# PISTA.net
KiCad netlist of a schematic drawn in EAGLE
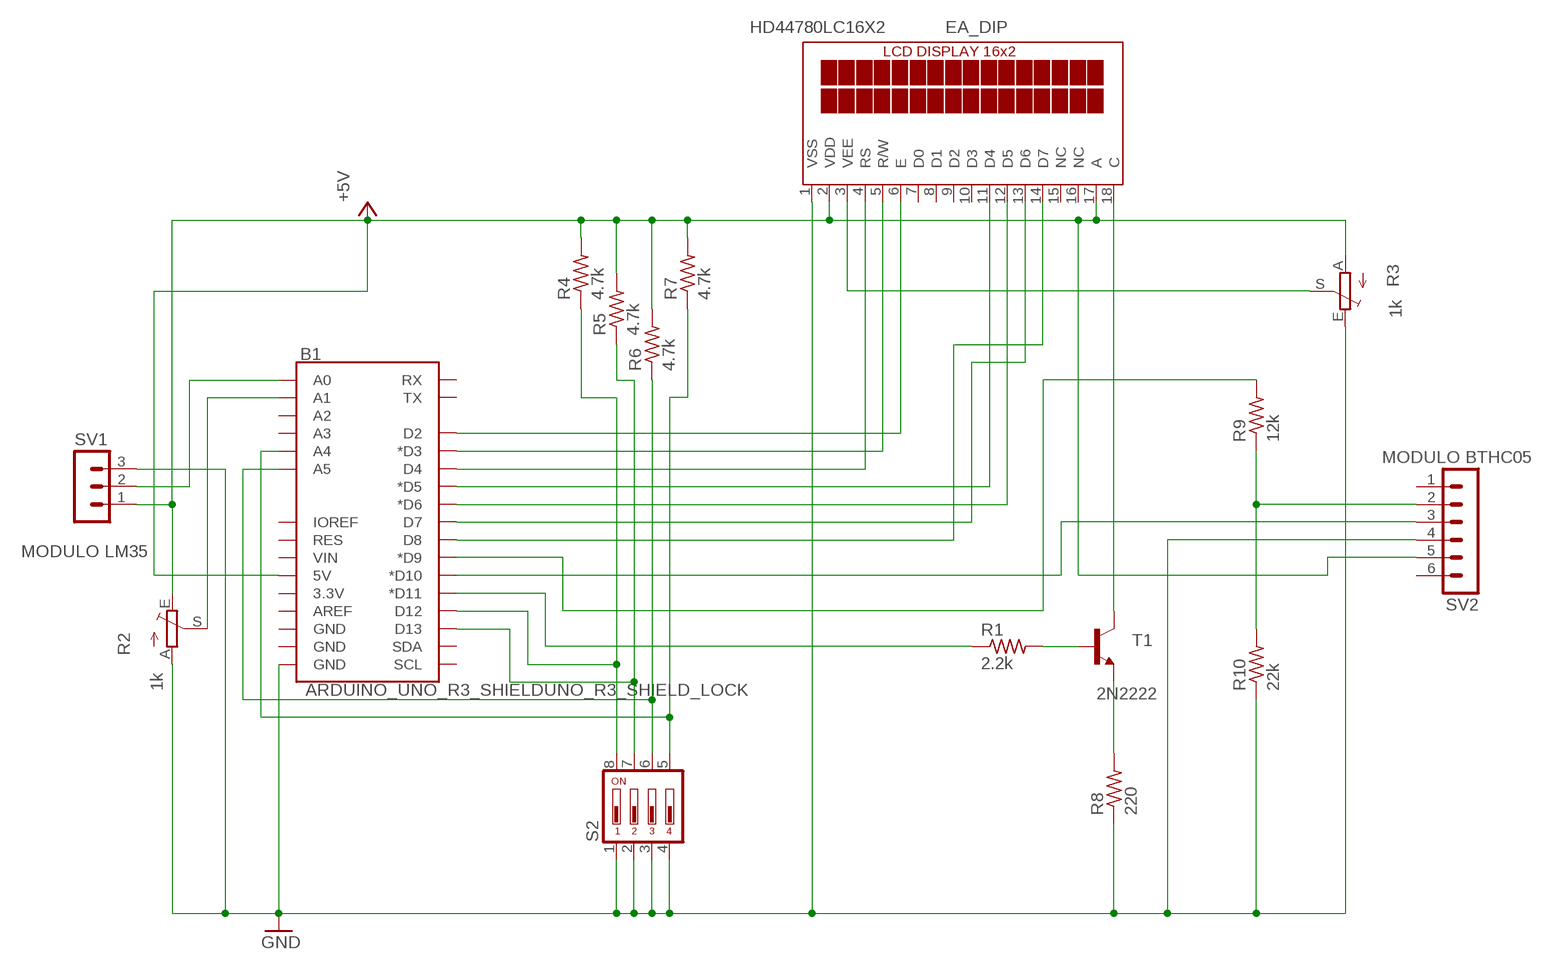
[diagram p0: schematic, sheet 1]

(export (version "E")
  (design (tool "Eeschema 10.0.6"))
  (components
    (comp (ref "B1")
      (value "ARDUINO_UNO_R3_SHIELDUNO_R3_SHIELD_LOCK")
      (footprint "eagle-import:UNO_R3_SHIELD_LOCK")
      (libsource (lib "eagle-import") (part "ARDUINO_UNO_R3_SHIELDUNO_R3_SHIELD_LOCK"))
    )
    (comp (ref "HD44780LC16X2")
      (value "EA_DIP")
      (footprint "eagle-import:EA_DIP")
      (libsource (lib "eagle-import") (part "EA_DIP"))
    )
    (comp (ref "R1")
      (value "2.2k")
      (footprint "eagle-import:0207_10")
      (libsource (lib "eagle-import") (part "R-US_0207/10"))
    )
    (comp (ref "R2")
      (value "1k")
      (footprint "eagle-import:B25P")
      (libsource (lib "eagle-import") (part "TRIM_EU-B25P"))
    )
    (comp (ref "R3")
      (value "1k")
      (footprint "eagle-import:B25P")
      (libsource (lib "eagle-import") (part "TRIM_EU-B25P"))
    )
    (comp (ref "R4")
      (value "4.7k")
      (footprint "eagle-import:0207_10")
      (libsource (lib "eagle-import") (part "R-US_0207/10"))
    )
    (comp (ref "R5")
      (value "4.7k")
      (footprint "eagle-import:0207_10")
      (libsource (lib "eagle-import") (part "R-US_0207/10"))
    )
    (comp (ref "R6")
      (value "4.7k")
      (footprint "eagle-import:0207_10")
      (libsource (lib "eagle-import") (part "R-US_0207/10"))
    )
    (comp (ref "R7")
      (value "4.7k")
      (footprint "eagle-import:0207_10")
      (libsource (lib "eagle-import") (part "R-US_0207/10"))
    )
    (comp (ref "R8")
      (value "220")
      (footprint "eagle-import:0207_10")
      (libsource (lib "eagle-import") (part "R-US_0207/10"))
    )
    (comp (ref "R9")
      (value "12k")
      (footprint "eagle-import:0207_10")
      (libsource (lib "eagle-import") (part "R-US_0207/10"))
    )
    (comp (ref "R10")
      (value "22k")
      (footprint "eagle-import:0207_10")
      (libsource (lib "eagle-import") (part "R-US_0207/10"))
    )
    (comp (ref "S2")
      (value "SD4-04")
      (footprint "eagle-import:SD4-04")
      (libsource (lib "eagle-import") (part "SD4-04"))
    )
    (comp (ref "SV1")
      (value "MODULO LM35")
      (footprint "eagle-import:MA03-1")
      (libsource (lib "eagle-import") (part "MA03-1"))
    )
    (comp (ref "SV2")
      (value "MODULO BTHC05")
      (footprint "eagle-import:MA06-1")
      (libsource (lib "eagle-import") (part "MA06-1"))
    )
    (comp (ref "T1")
      (value "2N2222")
      (footprint "eagle-import:TO18")
      (libsource (lib "eagle-import") (part "2N2222"))
    )
  )
  (nets
    (net (code "1") (name "+5V") (class "Default")
      (node (ref "B1") (pin "5V") (pinfunction "5V_5V") (pintype "bidirectional"))
      (node (ref "HD44780LC16X2") (pin "17") (pinfunction "A_17") (pintype "passive"))
      (node (ref "HD44780LC16X2") (pin "2") (pinfunction "VDD_2") (pintype "power_in"))
      (node (ref "R2") (pin "E") (pinfunction "E_E") (pintype "passive"))
      (node (ref "R3") (pin "A") (pinfunction "A_A") (pintype "passive"))
      (node (ref "R4") (pin "2") (pinfunction "2_2") (pintype "passive"))
      (node (ref "R5") (pin "2") (pinfunction "2_2") (pintype "passive"))
      (node (ref "R6") (pin "2") (pinfunction "2_2") (pintype "passive"))
      (node (ref "R7") (pin "2") (pinfunction "2_2") (pintype "passive"))
      (node (ref "SV1") (pin "1") (pinfunction "1_1") (pintype "passive"))
      (node (ref "SV2") (pin "5") (pinfunction "5_5") (pintype "passive"))
    )
    (net (code "2") (name "GND") (class "Default")
      (node (ref "B1") (pin "GND@0") (pinfunction "GND_GND@0") (pintype "bidirectional"))
      (node (ref "HD44780LC16X2") (pin "1") (pinfunction "VSS_1") (pintype "power_in"))
      (node (ref "R10") (pin "1") (pinfunction "1_1") (pintype "passive"))
      (node (ref "R2") (pin "A") (pinfunction "A_A") (pintype "passive"))
      (node (ref "R3") (pin "E") (pinfunction "E_E") (pintype "passive"))
      (node (ref "R8") (pin "1") (pinfunction "1_1") (pintype "passive"))
      (node (ref "S2") (pin "1") (pinfunction "1_1") (pintype "passive"))
      (node (ref "S2") (pin "2") (pinfunction "2_2") (pintype "passive"))
      (node (ref "S2") (pin "3") (pinfunction "3_3") (pintype "passive"))
      (node (ref "S2") (pin "4") (pinfunction "4_4") (pintype "passive"))
      (node (ref "SV1") (pin "3") (pinfunction "3_3") (pintype "passive"))
      (node (ref "SV2") (pin "4") (pinfunction "4_4") (pintype "passive"))
    )
    (net (code "3") (name "Net-(B1-*D3)") (class "Default")
      (node (ref "B1") (pin "D3") (pinfunction "*D3_D3") (pintype "bidirectional"))
      (node (ref "HD44780LC16X2") (pin "5") (pinfunction "R/W_5") (pintype "input"))
    )
    (net (code "4") (name "Net-(B1-*D5)") (class "Default")
      (node (ref "B1") (pin "D5") (pinfunction "*D5_D5") (pintype "bidirectional"))
      (node (ref "HD44780LC16X2") (pin "11") (pinfunction "D4_11") (pintype "input"))
    )
    (net (code "5") (name "Net-(B1-*D6)") (class "Default")
      (node (ref "B1") (pin "D6") (pinfunction "*D6_D6") (pintype "bidirectional"))
      (node (ref "HD44780LC16X2") (pin "12") (pinfunction "D5_12") (pintype "input"))
    )
    (net (code "6") (name "Net-(B1-*D9)") (class "Default")
      (node (ref "B1") (pin "D9") (pinfunction "*D9_D9") (pintype "bidirectional"))
      (node (ref "R9") (pin "2") (pinfunction "2_2") (pintype "passive"))
    )
    (net (code "7") (name "Net-(B1-*D10)") (class "Default")
      (node (ref "B1") (pin "D10") (pinfunction "*D10_D10") (pintype "bidirectional"))
      (node (ref "SV2") (pin "3") (pinfunction "3_3") (pintype "passive"))
    )
    (net (code "8") (name "Net-(B1-*D11)") (class "Default")
      (node (ref "B1") (pin "D11") (pinfunction "*D11_D11") (pintype "bidirectional"))
      (node (ref "R1") (pin "1") (pinfunction "1_1") (pintype "passive"))
    )
    (net (code "9") (name "Net-(B1-PadA0)") (class "Default")
      (node (ref "B1") (pin "A0") (pinfunction "A0_A0") (pintype "bidirectional"))
      (node (ref "SV1") (pin "2") (pinfunction "2_2") (pintype "passive"))
    )
    (net (code "10") (name "Net-(B1-PadA1)") (class "Default")
      (node (ref "B1") (pin "A1") (pinfunction "A1_A1") (pintype "bidirectional"))
      (node (ref "R2") (pin "S") (pinfunction "S_S") (pintype "passive"))
    )
    (net (code "11") (name "Net-(B1-PadA4)") (class "Default")
      (node (ref "B1") (pin "A4") (pinfunction "A4_A4") (pintype "bidirectional"))
      (node (ref "R7") (pin "1") (pinfunction "1_1") (pintype "passive"))
      (node (ref "S2") (pin "5") (pinfunction "5_5") (pintype "passive"))
    )
    (net (code "12") (name "Net-(B1-PadA5)") (class "Default")
      (node (ref "B1") (pin "A5") (pinfunction "A5_A5") (pintype "bidirectional"))
      (node (ref "R6") (pin "1") (pinfunction "1_1") (pintype "passive"))
      (node (ref "S2") (pin "6") (pinfunction "6_6") (pintype "passive"))
    )
    (net (code "13") (name "Net-(B1-PadD12)") (class "Default")
      (node (ref "B1") (pin "D12") (pinfunction "D12_D12") (pintype "bidirectional"))
      (node (ref "R4") (pin "1") (pinfunction "1_1") (pintype "passive"))
      (node (ref "S2") (pin "8") (pinfunction "8_8") (pintype "passive"))
    )
    (net (code "14") (name "Net-(B1-PadD13)") (class "Default")
      (node (ref "B1") (pin "D13") (pinfunction "D13_D13") (pintype "bidirectional"))
      (node (ref "R5") (pin "1") (pinfunction "1_1") (pintype "passive"))
      (node (ref "S2") (pin "7") (pinfunction "7_7") (pintype "passive"))
    )
    (net (code "15") (name "Net-(HD44780LC16X2-C)") (class "Default")
      (node (ref "HD44780LC16X2") (pin "18") (pinfunction "C_18") (pintype "passive"))
      (node (ref "T1") (pin "3") (pinfunction "C_3") (pintype "passive"))
    )
    (net (code "16") (name "Net-(HD44780LC16X2-D6)") (class "Default")
      (node (ref "B1") (pin "D7") (pinfunction "D7_D7") (pintype "bidirectional"))
      (node (ref "HD44780LC16X2") (pin "13") (pinfunction "D6_13") (pintype "input"))
    )
    (net (code "17") (name "Net-(HD44780LC16X2-D7)") (class "Default")
      (node (ref "B1") (pin "D8") (pinfunction "D8_D8") (pintype "bidirectional"))
      (node (ref "HD44780LC16X2") (pin "14") (pinfunction "D7_14") (pintype "input"))
    )
    (net (code "18") (name "Net-(HD44780LC16X2-E)") (class "Default")
      (node (ref "B1") (pin "D2") (pinfunction "D2_D2") (pintype "bidirectional"))
      (node (ref "HD44780LC16X2") (pin "6") (pinfunction "E_6") (pintype "input"))
    )
    (net (code "19") (name "Net-(HD44780LC16X2-RS)") (class "Default")
      (node (ref "B1") (pin "D4") (pinfunction "D4_D4") (pintype "bidirectional"))
      (node (ref "HD44780LC16X2") (pin "4") (pinfunction "RS_4") (pintype "input"))
    )
    (net (code "20") (name "Net-(HD44780LC16X2-VEE)") (class "Default")
      (node (ref "HD44780LC16X2") (pin "3") (pinfunction "VEE_3") (pintype "power_in"))
      (node (ref "R3") (pin "S") (pinfunction "S_S") (pintype "passive"))
    )
    (net (code "21") (name "Net-(R10-Pad2)") (class "Default")
      (node (ref "R10") (pin "2") (pinfunction "2_2") (pintype "passive"))
      (node (ref "R9") (pin "1") (pinfunction "1_1") (pintype "passive"))
      (node (ref "SV2") (pin "2") (pinfunction "2_2") (pintype "passive"))
    )
    (net (code "22") (name "Net-(T1-B)") (class "Default")
      (node (ref "R1") (pin "2") (pinfunction "2_2") (pintype "passive"))
      (node (ref "T1") (pin "2") (pinfunction "B_2") (pintype "passive"))
    )
    (net (code "23") (name "Net-(T1-E)") (class "Default")
      (node (ref "R8") (pin "2") (pinfunction "2_2") (pintype "passive"))
      (node (ref "T1") (pin "1") (pinfunction "E_1") (pintype "passive"))
    )
    (net (code "24") (name "unconnected-(B1-GND-PadGND@1)") (class "Default")
      (node (ref "B1") (pin "GND@1") (pinfunction "GND_GND@1") (pintype "bidirectional"))
    )
    (net (code "25") (name "unconnected-(B1-GND-PadGND@2)") (class "Default")
      (node (ref "B1") (pin "GND@2") (pinfunction "GND_GND@2") (pintype "bidirectional"))
    )
    (net (code "26") (name "unconnected-(B1-Pad3.3V)") (class "Default")
      (node (ref "B1") (pin "3.3V") (pinfunction "3.3V_3.3V") (pintype "bidirectional"))
    )
    (net (code "27") (name "unconnected-(B1-PadA2)") (class "Default")
      (node (ref "B1") (pin "A2") (pinfunction "A2_A2") (pintype "bidirectional"))
    )
    (net (code "28") (name "unconnected-(B1-PadA3)") (class "Default")
      (node (ref "B1") (pin "A3") (pinfunction "A3_A3") (pintype "bidirectional"))
    )
    (net (code "29") (name "unconnected-(B1-PadAREF)") (class "Default")
      (node (ref "B1") (pin "AREF") (pinfunction "AREF_AREF") (pintype "bidirectional"))
    )
    (net (code "30") (name "unconnected-(B1-PadIOREF)") (class "Default")
      (node (ref "B1") (pin "IOREF") (pinfunction "IOREF_IOREF") (pintype "bidirectional"))
    )
    (net (code "31") (name "unconnected-(B1-PadRES)") (class "Default")
      (node (ref "B1") (pin "RES") (pinfunction "RES_RES") (pintype "bidirectional"))
    )
    (net (code "32") (name "unconnected-(B1-PadRX)") (class "Default")
      (node (ref "B1") (pin "RX") (pinfunction "RX_RX") (pintype "bidirectional"))
    )
    (net (code "33") (name "unconnected-(B1-PadSCL)") (class "Default")
      (node (ref "B1") (pin "SCL") (pinfunction "SCL_SCL") (pintype "bidirectional"))
    )
    (net (code "34") (name "unconnected-(B1-PadSDA)") (class "Default")
      (node (ref "B1") (pin "SDA") (pinfunction "SDA_SDA") (pintype "bidirectional"))
    )
    (net (code "35") (name "unconnected-(B1-PadTX)") (class "Default")
      (node (ref "B1") (pin "TX") (pinfunction "TX_TX") (pintype "bidirectional"))
    )
    (net (code "36") (name "unconnected-(B1-PadVIN)") (class "Default")
      (node (ref "B1") (pin "VIN") (pinfunction "VIN_VIN") (pintype "bidirectional"))
    )
    (net (code "37") (name "unconnected-(HD44780LC16X2-D0-Pad7)") (class "Default")
      (node (ref "HD44780LC16X2") (pin "7") (pinfunction "D0_7") (pintype "input"))
    )
    (net (code "38") (name "unconnected-(HD44780LC16X2-D1-Pad8)") (class "Default")
      (node (ref "HD44780LC16X2") (pin "8") (pinfunction "D1_8") (pintype "input"))
    )
    (net (code "39") (name "unconnected-(HD44780LC16X2-D2-Pad9)") (class "Default")
      (node (ref "HD44780LC16X2") (pin "9") (pinfunction "D2_9") (pintype "input"))
    )
    (net (code "40") (name "unconnected-(HD44780LC16X2-D3-Pad10)") (class "Default")
      (node (ref "HD44780LC16X2") (pin "10") (pinfunction "D3_10") (pintype "input"))
    )
    (net (code "41") (name "unconnected-(HD44780LC16X2-NC-Pad15)") (class "Default")
      (node (ref "HD44780LC16X2") (pin "15") (pinfunction "NC_15") (pintype "no_connect"))
    )
    (net (code "42") (name "unconnected-(HD44780LC16X2-NC-Pad16)") (class "Default")
      (node (ref "HD44780LC16X2") (pin "16") (pinfunction "NC_16") (pintype "no_connect"))
    )
    (net (code "43") (name "unconnected-(SV2-Pad1)") (class "Default")
      (node (ref "SV2") (pin "1") (pinfunction "1_1") (pintype "passive"))
    )
    (net (code "44") (name "unconnected-(SV2-Pad6)") (class "Default")
      (node (ref "SV2") (pin "6") (pinfunction "6_6") (pintype "passive"))
    )
  )
)
